# wifi.net
KiCad netlist of a schematic drawn in Altium Designer
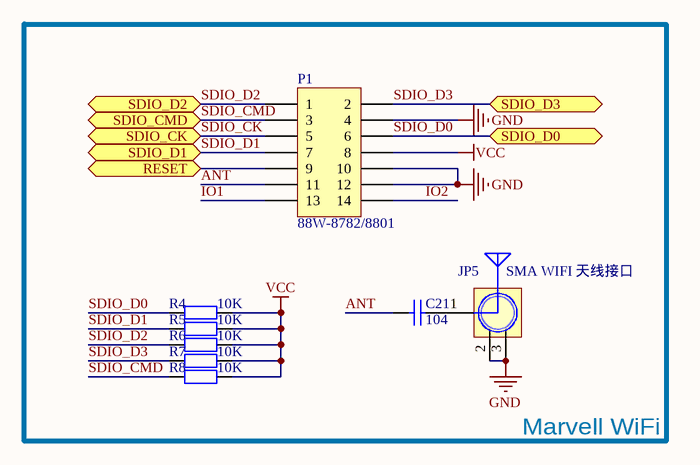
[diagram p0: wifi.SchDoc]

(export (version "E")
  (design (tool "Eeschema 10.0.6"))
  (components
    (comp (ref "C21")
      (value "104")
      (footprint "C 0603_L")
      (description "Capacitor")
      (fields (field (name "PUBLISHER") "Altium Limited"))
      (libsource (lib "Miscellaneous Devices") (part "Cap"))
    )
    (comp (ref "JP5")
      (value "SMA WIFI 天线接口")
      (footprint "SMA_FR")
      (description "SMA-2.4G射频天线接口")
      (fields (field (name "版权归属") "源创客"))
      (libsource (lib "14.1 - 天线") (part "SMA"))
    )
    (comp (ref "P1")
      (value "88W-8782/8801")
      (footprint "W8782_MODULE")
      (description "Header, 7-Pin, Dual row")
      (fields (field (name "PUBLISHER") "Altium Limited"))
      (libsource (lib "Miscellaneous Connectors") (part "Header 7X2"))
    )
    (comp (ref "R4")
      (value "10K")
      (footprint "R 0603_L")
      (description "Resistor")
      (fields (field (name "PUBLISHER") "Altium Limited"))
      (libsource (lib "Miscellaneous Devices") (part "Res2"))
    )
    (comp (ref "R5")
      (value "10K")
      (footprint "R 0603_L")
      (description "Resistor")
      (fields (field (name "PUBLISHER") "Altium Limited"))
      (libsource (lib "") (part "Res2_1"))
    )
    (comp (ref "R6")
      (value "10K")
      (footprint "R 0603_L")
      (description "Resistor")
      (fields (field (name "PUBLISHER") "Altium Limited"))
      (libsource (lib "") (part "Res2_1"))
    )
    (comp (ref "R7")
      (value "10K")
      (footprint "R 0603_L")
      (description "Resistor")
      (fields (field (name "PUBLISHER") "Altium Limited"))
      (libsource (lib "") (part "Res2_1"))
    )
    (comp (ref "R8")
      (value "10K")
      (footprint "R 0603_L")
      (description "Resistor")
      (fields (field (name "PUBLISHER") "Altium Limited"))
      (libsource (lib "") (part "Res2_1"))
    )
  )
  (nets
    (net (code "1") (name "/ANT") (class "Default")
      (node (ref "C21") (pin "2") (pinfunction "2_2") (pintype "passive"))
      (node (ref "P1") (pin "11") (pinfunction "11_11") (pintype "passive"))
    )
    (net (code "2") (name "/IO1") (class "Default")
      (node (ref "P1") (pin "13") (pinfunction "13_13") (pintype "passive"))
    )
    (net (code "3") (name "/IO2") (class "Default")
      (node (ref "P1") (pin "14") (pinfunction "14_14") (pintype "passive"))
    )
    (net (code "4") (name "/RESET") (class "Default")
      (node (ref "P1") (pin "9") (pinfunction "9_9") (pintype "passive"))
    )
    (net (code "5") (name "/SDIO_CK") (class "Default")
      (node (ref "P1") (pin "5") (pinfunction "5_5") (pintype "passive"))
    )
    (net (code "6") (name "/SDIO_CMD") (class "Default")
      (node (ref "P1") (pin "3") (pinfunction "3_3") (pintype "passive"))
      (node (ref "R8") (pin "1") (pinfunction "1_1") (pintype "passive"))
    )
    (net (code "7") (name "/SDIO_D0") (class "Default")
      (node (ref "P1") (pin "6") (pinfunction "6_6") (pintype "passive"))
      (node (ref "R4") (pin "2") (pinfunction "2_2") (pintype "passive"))
    )
    (net (code "8") (name "/SDIO_D1") (class "Default")
      (node (ref "P1") (pin "7") (pinfunction "7_7") (pintype "passive"))
      (node (ref "R5") (pin "1") (pinfunction "1_1") (pintype "passive"))
    )
    (net (code "9") (name "/SDIO_D2") (class "Default")
      (node (ref "P1") (pin "1") (pinfunction "1_1") (pintype "passive"))
      (node (ref "R6") (pin "1") (pinfunction "1_1") (pintype "passive"))
    )
    (net (code "10") (name "/SDIO_D3") (class "Default")
      (node (ref "P1") (pin "2") (pinfunction "2_2") (pintype "passive"))
      (node (ref "R7") (pin "1") (pinfunction "1_1") (pintype "passive"))
    )
    (net (code "11") (name "GND") (class "Default")
      (node (ref "JP5") (pin "2") (pinfunction "GND_2") (pintype "passive"))
      (node (ref "JP5") (pin "3") (pinfunction "GND_3") (pintype "passive"))
      (node (ref "P1") (pin "10") (pinfunction "10_10") (pintype "passive"))
      (node (ref "P1") (pin "12") (pinfunction "12_12") (pintype "passive"))
      (node (ref "P1") (pin "4") (pinfunction "4_4") (pintype "passive"))
    )
    (net (code "12") (name "Net-(JP5-ANT)") (class "Default")
      (node (ref "C21") (pin "1") (pinfunction "1_1") (pintype "passive"))
      (node (ref "JP5") (pin "1") (pinfunction "ANT_1") (pintype "passive"))
    )
    (net (code "13") (name "VCC") (class "Default")
      (node (ref "P1") (pin "8") (pinfunction "8_8") (pintype "passive"))
      (node (ref "R4") (pin "1") (pinfunction "1_1") (pintype "passive"))
      (node (ref "R5") (pin "2") (pinfunction "2_2") (pintype "passive"))
      (node (ref "R6") (pin "2") (pinfunction "2_2") (pintype "passive"))
      (node (ref "R7") (pin "2") (pinfunction "2_2") (pintype "passive"))
      (node (ref "R8") (pin "2") (pinfunction "2_2") (pintype "passive"))
    )
  )
)
